# 06-VIDEO_IN_ADC_2.net
KiCad netlist of a schematic drawn in Altium Designer
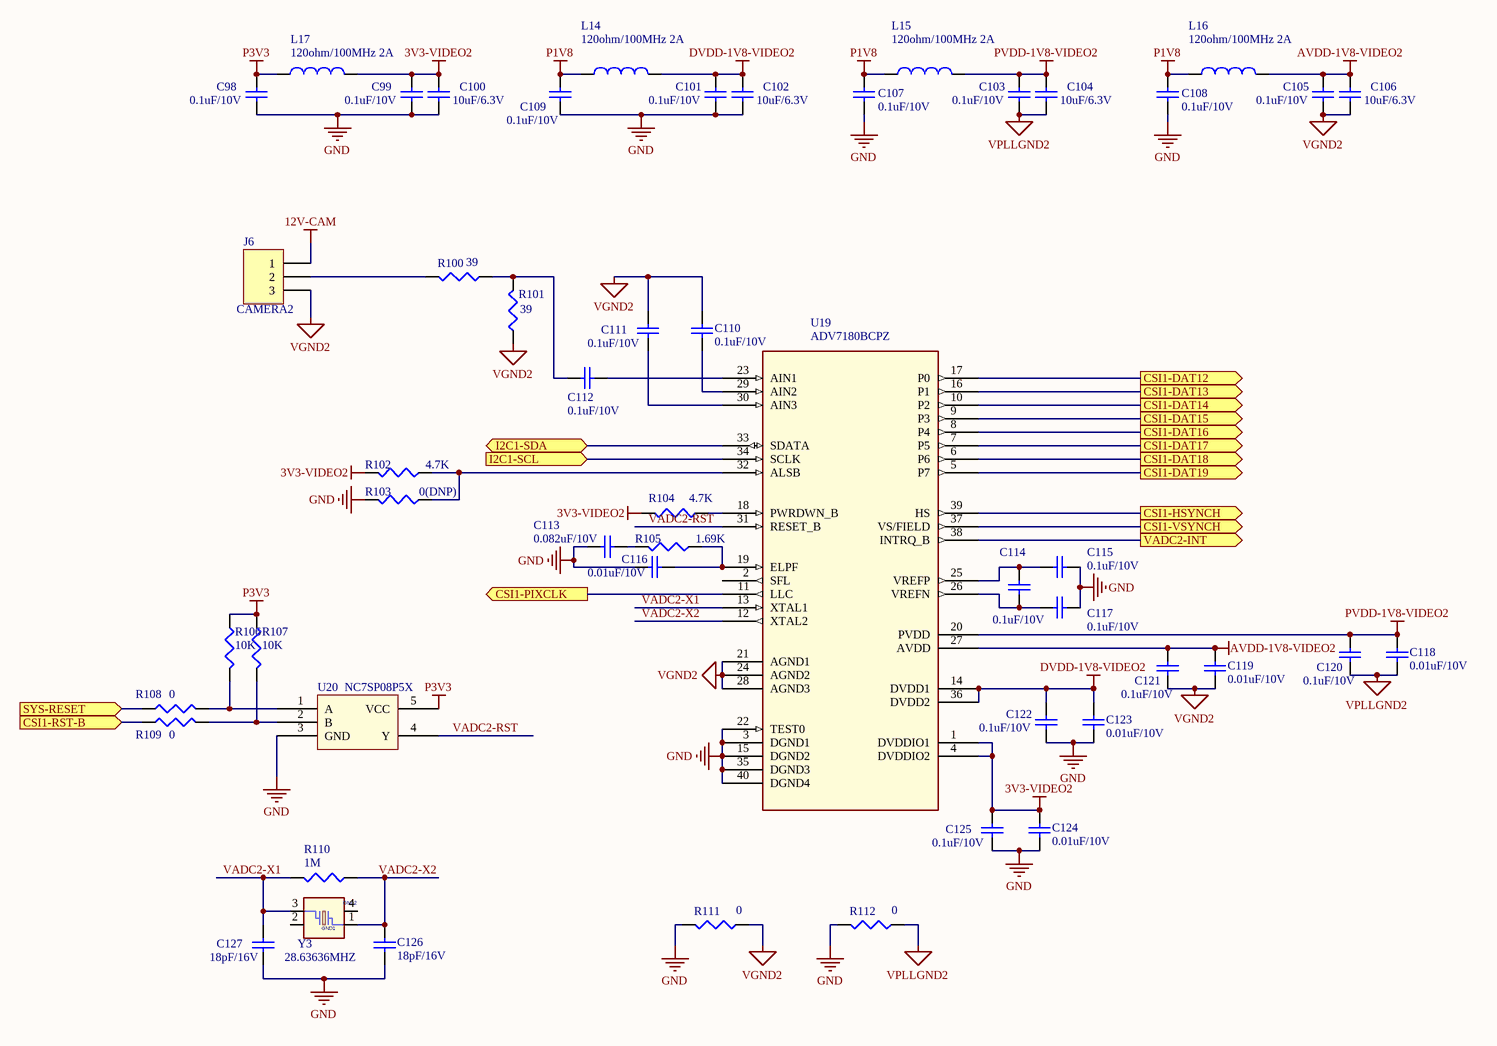
[diagram p0: 06-VIDEO_IN_ADC_2.SchDoc]

(export (version "E")
  (design (tool "Eeschema 10.0.6"))
  (components
    (comp (ref "C98")
      (value "0.1uF/10V")
      (footprint "0402")
      (description "Capacitor")
      (fields (field (name "PUBLISHER") "Altium Limited"))
      (libsource (lib "Miscellaneous Devices") (part "Cap"))
    )
    (comp (ref "C99")
      (value "0.1uF/10V")
      (footprint "0402")
      (description "Capacitor")
      (fields (field (name "PUBLISHER") "Altium Limited"))
      (libsource (lib "Miscellaneous Devices") (part "Cap"))
    )
    (comp (ref "C100")
      (value "10uF/6.3V")
      (footprint "0805")
      (description "Capacitor")
      (fields (field (name "PUBLISHER") "Altium Limited"))
      (libsource (lib "Miscellaneous Devices") (part "Cap"))
    )
    (comp (ref "C101")
      (value "0.1uF/10V")
      (footprint "0402")
      (description "Capacitor")
      (fields (field (name "PUBLISHER") "Altium Limited"))
      (libsource (lib "Miscellaneous Devices") (part "Cap"))
    )
    (comp (ref "C102")
      (value "10uF/6.3V")
      (footprint "0805")
      (description "Capacitor")
      (fields (field (name "PUBLISHER") "Altium Limited"))
      (libsource (lib "Miscellaneous Devices") (part "Cap"))
    )
    (comp (ref "C103")
      (value "0.1uF/10V")
      (footprint "0402")
      (description "Capacitor")
      (fields (field (name "PUBLISHER") "Altium Limited"))
      (libsource (lib "Miscellaneous Devices") (part "Cap"))
    )
    (comp (ref "C104")
      (value "10uF/6.3V")
      (footprint "0805")
      (description "Capacitor")
      (fields (field (name "PUBLISHER") "Altium Limited"))
      (libsource (lib "Miscellaneous Devices") (part "Cap"))
    )
    (comp (ref "C105")
      (value "0.1uF/10V")
      (footprint "0402")
      (description "Capacitor")
      (fields (field (name "PUBLISHER") "Altium Limited"))
      (libsource (lib "Miscellaneous Devices") (part "Cap"))
    )
    (comp (ref "C106")
      (value "10uF/6.3V")
      (footprint "0805")
      (description "Capacitor")
      (fields (field (name "PUBLISHER") "Altium Limited"))
      (libsource (lib "Miscellaneous Devices") (part "Cap"))
    )
    (comp (ref "C107")
      (value "0.1uF/10V")
      (footprint "0402")
      (description "Capacitor")
      (fields (field (name "PUBLISHER") "Altium Limited"))
      (libsource (lib "Miscellaneous Devices") (part "Cap"))
    )
    (comp (ref "C108")
      (value "0.1uF/10V")
      (footprint "0402")
      (description "Capacitor")
      (fields (field (name "PUBLISHER") "Altium Limited"))
      (libsource (lib "Miscellaneous Devices") (part "Cap"))
    )
    (comp (ref "C109")
      (value "0.1uF/10V")
      (footprint "0402")
      (description "Capacitor")
      (fields (field (name "PUBLISHER") "Altium Limited"))
      (libsource (lib "Miscellaneous Devices") (part "Cap"))
    )
    (comp (ref "C110")
      (value "0.1uF/10V")
      (footprint "0402")
      (description "Capacitor")
      (fields (field (name "PUBLISHER") "Altium Limited"))
      (libsource (lib "Miscellaneous Devices") (part "Cap"))
    )
    (comp (ref "C111")
      (value "0.1uF/10V")
      (footprint "0402")
      (description "Capacitor")
      (fields (field (name "PUBLISHER") "Altium Limited"))
      (libsource (lib "Miscellaneous Devices") (part "Cap"))
    )
    (comp (ref "C112")
      (value "0.1uF/10V")
      (footprint "0402")
      (description "Capacitor")
      (fields (field (name "PUBLISHER") "Altium Limited"))
      (libsource (lib "Miscellaneous Devices") (part "Cap"))
    )
    (comp (ref "C113")
      (value "0.082uF/10V")
      (footprint "0402")
      (description "Capacitor")
      (fields (field (name "PUBLISHER") "Altium Limited"))
      (libsource (lib "Miscellaneous Devices") (part "Cap"))
    )
    (comp (ref "C114")
      (value "0.1uF/10V")
      (footprint "0402")
      (description "Capacitor")
      (fields (field (name "PUBLISHER") "Altium Limited"))
      (libsource (lib "Miscellaneous Devices") (part "Cap"))
    )
    (comp (ref "C115")
      (value "0.1uF/10V")
      (footprint "0402")
      (description "Capacitor")
      (fields (field (name "PUBLISHER") "Altium Limited"))
      (libsource (lib "Miscellaneous Devices") (part "Cap"))
    )
    (comp (ref "C116")
      (value "0.01uF/10V")
      (footprint "0402")
      (description "Capacitor")
      (fields (field (name "PUBLISHER") "Altium Limited"))
      (libsource (lib "Miscellaneous Devices") (part "Cap"))
    )
    (comp (ref "C117")
      (value "0.1uF/10V")
      (footprint "0402")
      (description "Capacitor")
      (fields (field (name "PUBLISHER") "Altium Limited"))
      (libsource (lib "Miscellaneous Devices") (part "Cap"))
    )
    (comp (ref "C118")
      (value "0.01uF/10V")
      (footprint "0402")
      (description "Capacitor")
      (fields (field (name "PUBLISHER") "Altium Limited"))
      (libsource (lib "Miscellaneous Devices") (part "Cap"))
    )
    (comp (ref "C119")
      (value "0.01uF/10V")
      (footprint "0402")
      (description "Capacitor")
      (fields (field (name "PUBLISHER") "Altium Limited"))
      (libsource (lib "Miscellaneous Devices") (part "Cap"))
    )
    (comp (ref "C120")
      (value "0.1uF/10V")
      (footprint "0402")
      (description "Capacitor")
      (fields (field (name "PUBLISHER") "Altium Limited"))
      (libsource (lib "Miscellaneous Devices") (part "Cap"))
    )
    (comp (ref "C121")
      (value "0.1uF/10V")
      (footprint "0402")
      (description "Capacitor")
      (fields (field (name "PUBLISHER") "Altium Limited"))
      (libsource (lib "Miscellaneous Devices") (part "Cap"))
    )
    (comp (ref "C122")
      (value "0.1uF/10V")
      (footprint "0402")
      (description "Capacitor")
      (fields (field (name "PUBLISHER") "Altium Limited"))
      (libsource (lib "Miscellaneous Devices") (part "Cap"))
    )
    (comp (ref "C123")
      (value "0.01uF/10V")
      (footprint "0402")
      (description "Capacitor")
      (fields (field (name "PUBLISHER") "Altium Limited"))
      (libsource (lib "Miscellaneous Devices") (part "Cap"))
    )
    (comp (ref "C124")
      (value "0.01uF/10V")
      (footprint "0402")
      (description "Capacitor")
      (fields (field (name "PUBLISHER") "Altium Limited"))
      (libsource (lib "Miscellaneous Devices") (part "Cap"))
    )
    (comp (ref "C125")
      (value "0.1uF/10V")
      (footprint "0402")
      (description "Capacitor")
      (fields (field (name "PUBLISHER") "Altium Limited"))
      (libsource (lib "Miscellaneous Devices") (part "Cap"))
    )
    (comp (ref "C126")
      (value "18pF/16V")
      (footprint "0402")
      (description "Capacitor")
      (fields (field (name "PUBLISHER") "Altium Limited"))
      (libsource (lib "Miscellaneous Devices") (part "Cap"))
    )
    (comp (ref "C127")
      (value "18pF/16V")
      (footprint "0402")
      (description "Capacitor")
      (fields (field (name "PUBLISHER") "Altium Limited"))
      (libsource (lib "Miscellaneous Devices") (part "Cap"))
    )
    (comp (ref "J6")
      (value "CAMERA2")
      (footprint "CONN-3P")
      (description "Header, 3-Pin")
      (fields (field (name "PUBLISHER") "Altium Limited"))
      (libsource (lib "Miscellaneous Connectors") (part "Header 3"))
    )
    (comp (ref "L14")
      (value "120ohm/100MHz 2A")
      (footprint "0603")
      (description "Inductor")
      (fields (field (name "PUBLISHER") "Altium Limited"))
      (libsource (lib "Miscellaneous Devices") (part "Inductor"))
    )
    (comp (ref "L15")
      (value "120ohm/100MHz 2A")
      (footprint "0603")
      (description "Inductor")
      (fields (field (name "PUBLISHER") "Altium Limited"))
      (libsource (lib "Miscellaneous Devices") (part "Inductor"))
    )
    (comp (ref "L16")
      (value "120ohm/100MHz 2A")
      (footprint "0603")
      (description "Inductor")
      (fields (field (name "PUBLISHER") "Altium Limited"))
      (libsource (lib "Miscellaneous Devices") (part "Inductor"))
    )
    (comp (ref "L17")
      (value "120ohm/100MHz 2A")
      (footprint "0603")
      (description "Inductor")
      (fields (field (name "PUBLISHER") "Altium Limited"))
      (libsource (lib "Miscellaneous Devices") (part "Inductor"))
    )
    (comp (ref "R100") (value "39") (footprint "0402") (libsource (lib "*") (part "CR16-1003FM")))
    (comp (ref "R101") (value "39") (footprint "0402") (libsource (lib "*") (part "CR16-1003FM")))
    (comp (ref "R102") (value "4.7K") (footprint "0402") (libsource (lib "*") (part "CR16-1003FM")))
    (comp (ref "R103") (value "0(DNP)") (footprint "0402") (libsource (lib "*") (part "CR16-1003FM")))
    (comp (ref "R104") (value "4.7K") (footprint "0402") (libsource (lib "*") (part "CR16-1003FM")))
    (comp (ref "R105") (value "1.69K") (footprint "0402") (libsource (lib "*") (part "CR16-1003FM")))
    (comp (ref "R106") (value "10K") (footprint "0402") (libsource (lib "*") (part "CR16-1003FM")))
    (comp (ref "R107") (value "10K") (footprint "0402") (libsource (lib "*") (part "CR16-1003FM")))
    (comp (ref "R108") (value "0") (footprint "0402") (libsource (lib "*") (part "CR16-1003FM")))
    (comp (ref "R109") (value "0") (footprint "0402") (libsource (lib "*") (part "CR16-1003FM")))
    (comp (ref "R110") (value "1M") (footprint "0402") (libsource (lib "*") (part "CR16-1003FM")))
    (comp (ref "R111") (value "0") (footprint "0402") (libsource (lib "*") (part "CR16-1003FM")))
    (comp (ref "R112") (value "0") (footprint "0402") (libsource (lib "*") (part "CR16-1003FM")))
    (comp (ref "U19")
      (value "ADV7180BCPZ")
      (footprint "LFCSP40")
      (libsource (lib "Schlib") (part "ADV7180BCPZ"))
    )
    (comp (ref "U20") (value "NC7SP08P5X") (footprint "SC70") (libsource (lib "Schlib") (part "NC7SP08P5X")))
    (comp (ref "Y3")
      (value "28.63636MHZ")
      (footprint "XTAL4_SX_3225")
      (description "XTAL 28.63636MHZ 10PF RSN -- SMT")
      (libsource (lib "*") (part "CRYSTAL_JXS63"))
    )
  )
  (nets
    (net (code "1") (name "/CSI1-DAT12") (class "Default")
      (node (ref "U19") (pin "17") (pinfunction "P0_17") (pintype "output"))
    )
    (net (code "2") (name "/CSI1-DAT13") (class "Default")
      (node (ref "U19") (pin "16") (pinfunction "P1_16") (pintype "output"))
    )
    (net (code "3") (name "/CSI1-DAT14") (class "Default")
      (node (ref "U19") (pin "10") (pinfunction "P2_10") (pintype "output"))
    )
    (net (code "4") (name "/CSI1-DAT15") (class "Default")
      (node (ref "U19") (pin "9") (pinfunction "P3_9") (pintype "output"))
    )
    (net (code "5") (name "/CSI1-DAT16") (class "Default")
      (node (ref "U19") (pin "8") (pinfunction "P4_8") (pintype "output"))
    )
    (net (code "6") (name "/CSI1-DAT17") (class "Default")
      (node (ref "U19") (pin "7") (pinfunction "P5_7") (pintype "output"))
    )
    (net (code "7") (name "/CSI1-DAT18") (class "Default")
      (node (ref "U19") (pin "6") (pinfunction "P6_6") (pintype "output"))
    )
    (net (code "8") (name "/CSI1-DAT19") (class "Default")
      (node (ref "U19") (pin "5") (pinfunction "P7_5") (pintype "output"))
    )
    (net (code "9") (name "/CSI1-HSYNCH") (class "Default")
      (node (ref "U19") (pin "39") (pinfunction "HS_39") (pintype "output"))
    )
    (net (code "10") (name "/CSI1-PIXCLK") (class "Default")
      (node (ref "U19") (pin "11") (pinfunction "LLC_11") (pintype "output"))
    )
    (net (code "11") (name "/CSI1-RST-B") (class "Default")
      (node (ref "R109") (pin "1") (pinfunction "1_1") (pintype "passive"))
    )
    (net (code "12") (name "/CSI1-VSYNCH") (class "Default")
      (node (ref "U19") (pin "37") (pinfunction "VS/FIELD_37") (pintype "output"))
    )
    (net (code "13") (name "/I2C1-SCL") (class "Default")
      (node (ref "U19") (pin "34") (pinfunction "SCLK_34") (pintype "input"))
    )
    (net (code "14") (name "/I2C1-SDA") (class "Default")
      (node (ref "U19") (pin "33") (pinfunction "SDATA_33") (pintype "bidirectional"))
    )
    (net (code "15") (name "/SYS-RESET") (class "Default")
      (node (ref "R108") (pin "1") (pinfunction "1_1") (pintype "passive"))
    )
    (net (code "16") (name "/VADC2-INT") (class "Default")
      (node (ref "U19") (pin "38") (pinfunction "INTRQ_B_38") (pintype "output"))
    )
    (net (code "17") (name "/VADC2-RST") (class "Default")
      (node (ref "U19") (pin "31") (pinfunction "RESET_B_31") (pintype "input"))
      (node (ref "U20") (pin "4") (pinfunction "Y_4") (pintype "passive"))
    )
    (net (code "18") (name "/VADC2-X1") (class "Default")
      (node (ref "C127") (pin "2") (pinfunction "2_2") (pintype "passive"))
      (node (ref "R110") (pin "2") (pinfunction "2_2") (pintype "passive"))
      (node (ref "U19") (pin "13") (pinfunction "XTAL1_13") (pintype "input"))
      (node (ref "Y3") (pin "3") (pinfunction "3_3") (pintype "passive"))
    )
    (net (code "19") (name "/VADC2-X2") (class "Default")
      (node (ref "C126") (pin "2") (pinfunction "2_2") (pintype "passive"))
      (node (ref "R110") (pin "1") (pinfunction "1_1") (pintype "passive"))
      (node (ref "U19") (pin "12") (pinfunction "XTAL2_12") (pintype "output"))
      (node (ref "Y3") (pin "1") (pinfunction "1_1") (pintype "passive"))
    )
    (net (code "20") (name "3V3-VIDEO2") (class "Default")
      (node (ref "C100") (pin "1") (pinfunction "1_1") (pintype "passive"))
      (node (ref "C124") (pin "2") (pinfunction "2_2") (pintype "passive"))
      (node (ref "C125") (pin "2") (pinfunction "2_2") (pintype "passive"))
      (node (ref "C99") (pin "1") (pinfunction "1_1") (pintype "passive"))
      (node (ref "L17") (pin "2") (pinfunction "2_2") (pintype "passive"))
      (node (ref "R102") (pin "2") (pinfunction "2_2") (pintype "passive"))
      (node (ref "R104") (pin "2") (pinfunction "2_2") (pintype "passive"))
      (node (ref "U19") (pin "1") (pinfunction "DVDDIO1_1") (pintype "power_in"))
      (node (ref "U19") (pin "4") (pinfunction "DVDDIO2_4") (pintype "power_in"))
    )
    (net (code "21") (name "12V-CAM") (class "Default")
      (node (ref "J6") (pin "1") (pinfunction "1_1") (pintype "passive"))
    )
    (net (code "22") (name "AVDD-1V8-VIDEO2") (class "Default")
      (node (ref "C105") (pin "1") (pinfunction "1_1") (pintype "passive"))
      (node (ref "C106") (pin "1") (pinfunction "1_1") (pintype "passive"))
      (node (ref "C119") (pin "2") (pinfunction "2_2") (pintype "passive"))
      (node (ref "C121") (pin "2") (pinfunction "2_2") (pintype "passive"))
      (node (ref "L16") (pin "2") (pinfunction "2_2") (pintype "passive"))
      (node (ref "U19") (pin "27") (pinfunction "AVDD_27") (pintype "power_in"))
    )
    (net (code "23") (name "DVDD-1V8-VIDEO2") (class "Default")
      (node (ref "C101") (pin "1") (pinfunction "1_1") (pintype "passive"))
      (node (ref "C102") (pin "1") (pinfunction "1_1") (pintype "passive"))
      (node (ref "C122") (pin "2") (pinfunction "2_2") (pintype "passive"))
      (node (ref "C123") (pin "2") (pinfunction "2_2") (pintype "passive"))
      (node (ref "L14") (pin "2") (pinfunction "2_2") (pintype "passive"))
      (node (ref "U19") (pin "14") (pinfunction "DVDD1_14") (pintype "power_in"))
      (node (ref "U19") (pin "36") (pinfunction "DVDD2_36") (pintype "power_in"))
    )
    (net (code "24") (name "GND") (class "Default")
      (node (ref "C100") (pin "2") (pinfunction "2_2") (pintype "passive"))
      (node (ref "C101") (pin "2") (pinfunction "2_2") (pintype "passive"))
      (node (ref "C102") (pin "2") (pinfunction "2_2") (pintype "passive"))
      (node (ref "C107") (pin "2") (pinfunction "2_2") (pintype "passive"))
      (node (ref "C108") (pin "2") (pinfunction "2_2") (pintype "passive"))
      (node (ref "C109") (pin "2") (pinfunction "2_2") (pintype "passive"))
      (node (ref "C113") (pin "1") (pinfunction "1_1") (pintype "passive"))
      (node (ref "C115") (pin "1") (pinfunction "1_1") (pintype "passive"))
      (node (ref "C116") (pin "1") (pinfunction "1_1") (pintype "passive"))
      (node (ref "C117") (pin "2") (pinfunction "2_2") (pintype "passive"))
      (node (ref "C122") (pin "1") (pinfunction "1_1") (pintype "passive"))
      (node (ref "C123") (pin "1") (pinfunction "1_1") (pintype "passive"))
      (node (ref "C124") (pin "1") (pinfunction "1_1") (pintype "passive"))
      (node (ref "C125") (pin "1") (pinfunction "1_1") (pintype "passive"))
      (node (ref "C126") (pin "1") (pinfunction "1_1") (pintype "passive"))
      (node (ref "C127") (pin "1") (pinfunction "1_1") (pintype "passive"))
      (node (ref "C98") (pin "2") (pinfunction "2_2") (pintype "passive"))
      (node (ref "C99") (pin "2") (pinfunction "2_2") (pintype "passive"))
      (node (ref "R103") (pin "2") (pinfunction "2_2") (pintype "passive"))
      (node (ref "R111") (pin "2") (pinfunction "2_2") (pintype "passive"))
      (node (ref "R112") (pin "2") (pinfunction "2_2") (pintype "passive"))
      (node (ref "U19") (pin "15") (pinfunction "DGND2_15") (pintype "power_in"))
      (node (ref "U19") (pin "22") (pinfunction "TEST0_22") (pintype "input"))
      (node (ref "U19") (pin "3") (pinfunction "DGND1_3") (pintype "power_in"))
      (node (ref "U19") (pin "35") (pinfunction "DGND3_35") (pintype "power_in"))
      (node (ref "U19") (pin "40") (pinfunction "DGND4_40") (pintype "power_in"))
      (node (ref "U20") (pin "3") (pinfunction "GND_3") (pintype "passive"))
    )
    (net (code "25") (name "Net-(C112-Pad1)") (class "Default")
      (node (ref "C112") (pin "1") (pinfunction "1_1") (pintype "passive"))
      (node (ref "R100") (pin "1") (pinfunction "1_1") (pintype "passive"))
      (node (ref "R101") (pin "2") (pinfunction "2_2") (pintype "passive"))
    )
    (net (code "26") (name "Net-(C113-Pad2)") (class "Default")
      (node (ref "C113") (pin "2") (pinfunction "2_2") (pintype "passive"))
      (node (ref "R105") (pin "2") (pinfunction "2_2") (pintype "passive"))
    )
    (net (code "27") (name "Net-(J6-Pad2)") (class "Default")
      (node (ref "J6") (pin "2") (pinfunction "2_2") (pintype "passive"))
      (node (ref "R100") (pin "2") (pinfunction "2_2") (pintype "passive"))
    )
    (net (code "28") (name "Net-(U19-AIN1)") (class "Default")
      (node (ref "C112") (pin "2") (pinfunction "2_2") (pintype "passive"))
      (node (ref "U19") (pin "23") (pinfunction "AIN1_23") (pintype "input"))
    )
    (net (code "29") (name "Net-(U19-AIN2)") (class "Default")
      (node (ref "C110") (pin "1") (pinfunction "1_1") (pintype "passive"))
      (node (ref "U19") (pin "29") (pinfunction "AIN2_29") (pintype "input"))
    )
    (net (code "30") (name "Net-(U19-AIN3)") (class "Default")
      (node (ref "C111") (pin "1") (pinfunction "1_1") (pintype "passive"))
      (node (ref "U19") (pin "30") (pinfunction "AIN3_30") (pintype "input"))
    )
    (net (code "31") (name "Net-(U19-ALSB)") (class "Default")
      (node (ref "R102") (pin "1") (pinfunction "1_1") (pintype "passive"))
      (node (ref "R103") (pin "1") (pinfunction "1_1") (pintype "passive"))
      (node (ref "U19") (pin "32") (pinfunction "ALSB_32") (pintype "input"))
    )
    (net (code "32") (name "Net-(U19-ELPF)") (class "Default")
      (node (ref "C116") (pin "2") (pinfunction "2_2") (pintype "passive"))
      (node (ref "R105") (pin "1") (pinfunction "1_1") (pintype "passive"))
      (node (ref "U19") (pin "19") (pinfunction "ELPF_19") (pintype "input"))
    )
    (net (code "33") (name "Net-(U19-PWRDWN_B)") (class "Default")
      (node (ref "R104") (pin "1") (pinfunction "1_1") (pintype "passive"))
      (node (ref "U19") (pin "18") (pinfunction "PWRDWN_B_18") (pintype "input"))
    )
    (net (code "34") (name "Net-(U19-VREFN)") (class "Default")
      (node (ref "C114") (pin "1") (pinfunction "1_1") (pintype "passive"))
      (node (ref "C117") (pin "1") (pinfunction "1_1") (pintype "passive"))
      (node (ref "U19") (pin "26") (pinfunction "VREFN_26") (pintype "output"))
    )
    (net (code "35") (name "Net-(U19-VREFP)") (class "Default")
      (node (ref "C114") (pin "2") (pinfunction "2_2") (pintype "passive"))
      (node (ref "C115") (pin "2") (pinfunction "2_2") (pintype "passive"))
      (node (ref "U19") (pin "25") (pinfunction "VREFP_25") (pintype "output"))
    )
    (net (code "36") (name "Net-(U20-A)") (class "Default")
      (node (ref "R106") (pin "2") (pinfunction "2_2") (pintype "passive"))
      (node (ref "R108") (pin "2") (pinfunction "2_2") (pintype "passive"))
      (node (ref "U20") (pin "1") (pinfunction "A_1") (pintype "passive"))
    )
    (net (code "37") (name "Net-(U20-B)") (class "Default")
      (node (ref "R107") (pin "2") (pinfunction "2_2") (pintype "passive"))
      (node (ref "R109") (pin "2") (pinfunction "2_2") (pintype "passive"))
      (node (ref "U20") (pin "2") (pinfunction "B_2") (pintype "passive"))
    )
    (net (code "38") (name "P1V8") (class "Default")
      (node (ref "C107") (pin "1") (pinfunction "1_1") (pintype "passive"))
      (node (ref "C108") (pin "1") (pinfunction "1_1") (pintype "passive"))
      (node (ref "C109") (pin "1") (pinfunction "1_1") (pintype "passive"))
      (node (ref "L14") (pin "1") (pinfunction "1_1") (pintype "passive"))
      (node (ref "L15") (pin "1") (pinfunction "1_1") (pintype "passive"))
      (node (ref "L16") (pin "1") (pinfunction "1_1") (pintype "passive"))
    )
    (net (code "39") (name "P3V3") (class "Default")
      (node (ref "C98") (pin "1") (pinfunction "1_1") (pintype "passive"))
      (node (ref "L17") (pin "1") (pinfunction "1_1") (pintype "passive"))
      (node (ref "R106") (pin "1") (pinfunction "1_1") (pintype "passive"))
      (node (ref "R107") (pin "1") (pinfunction "1_1") (pintype "passive"))
      (node (ref "U20") (pin "5") (pinfunction "VCC_5") (pintype "passive"))
    )
    (net (code "40") (name "PVDD-1V8-VIDEO2") (class "Default")
      (node (ref "C103") (pin "1") (pinfunction "1_1") (pintype "passive"))
      (node (ref "C104") (pin "1") (pinfunction "1_1") (pintype "passive"))
      (node (ref "C118") (pin "2") (pinfunction "2_2") (pintype "passive"))
      (node (ref "C120") (pin "2") (pinfunction "2_2") (pintype "passive"))
      (node (ref "L15") (pin "2") (pinfunction "2_2") (pintype "passive"))
      (node (ref "U19") (pin "20") (pinfunction "PVDD_20") (pintype "power_in"))
    )
    (net (code "41") (name "VGND2") (class "Default")
      (node (ref "C105") (pin "2") (pinfunction "2_2") (pintype "passive"))
      (node (ref "C106") (pin "2") (pinfunction "2_2") (pintype "passive"))
      (node (ref "C110") (pin "2") (pinfunction "2_2") (pintype "passive"))
      (node (ref "C111") (pin "2") (pinfunction "2_2") (pintype "passive"))
      (node (ref "C119") (pin "1") (pinfunction "1_1") (pintype "passive"))
      (node (ref "C121") (pin "1") (pinfunction "1_1") (pintype "passive"))
      (node (ref "J6") (pin "3") (pinfunction "3_3") (pintype "passive"))
      (node (ref "R101") (pin "1") (pinfunction "1_1") (pintype "passive"))
      (node (ref "R111") (pin "1") (pinfunction "1_1") (pintype "passive"))
      (node (ref "U19") (pin "21") (pinfunction "AGND1_21") (pintype "power_in"))
      (node (ref "U19") (pin "24") (pinfunction "AGND2_24") (pintype "power_in"))
      (node (ref "U19") (pin "28") (pinfunction "AGND3_28") (pintype "power_in"))
    )
    (net (code "42") (name "VPLLGND2") (class "Default")
      (node (ref "C103") (pin "2") (pinfunction "2_2") (pintype "passive"))
      (node (ref "C104") (pin "2") (pinfunction "2_2") (pintype "passive"))
      (node (ref "C118") (pin "1") (pinfunction "1_1") (pintype "passive"))
      (node (ref "C120") (pin "1") (pinfunction "1_1") (pintype "passive"))
      (node (ref "R112") (pin "1") (pinfunction "1_1") (pintype "passive"))
    )
    (net (code "43") (name "unconnected-(U19-SFL-Pad2)") (class "Default")
      (node (ref "U19") (pin "2") (pinfunction "SFL_2") (pintype "output"))
    )
    (net (code "44") (name "unconnected-(Y3-GND1-Pad2)") (class "Default")
      (node (ref "Y3") (pin "2") (pinfunction "GND1_2") (pintype "power_in"))
    )
    (net (code "45") (name "unconnected-(Y3-GND2-Pad4)") (class "Default")
      (node (ref "Y3") (pin "4") (pinfunction "GND2_4") (pintype "power_in"))
    )
  )
)
